# Actuator.net
KiCad netlist of a schematic drawn in EAGLE
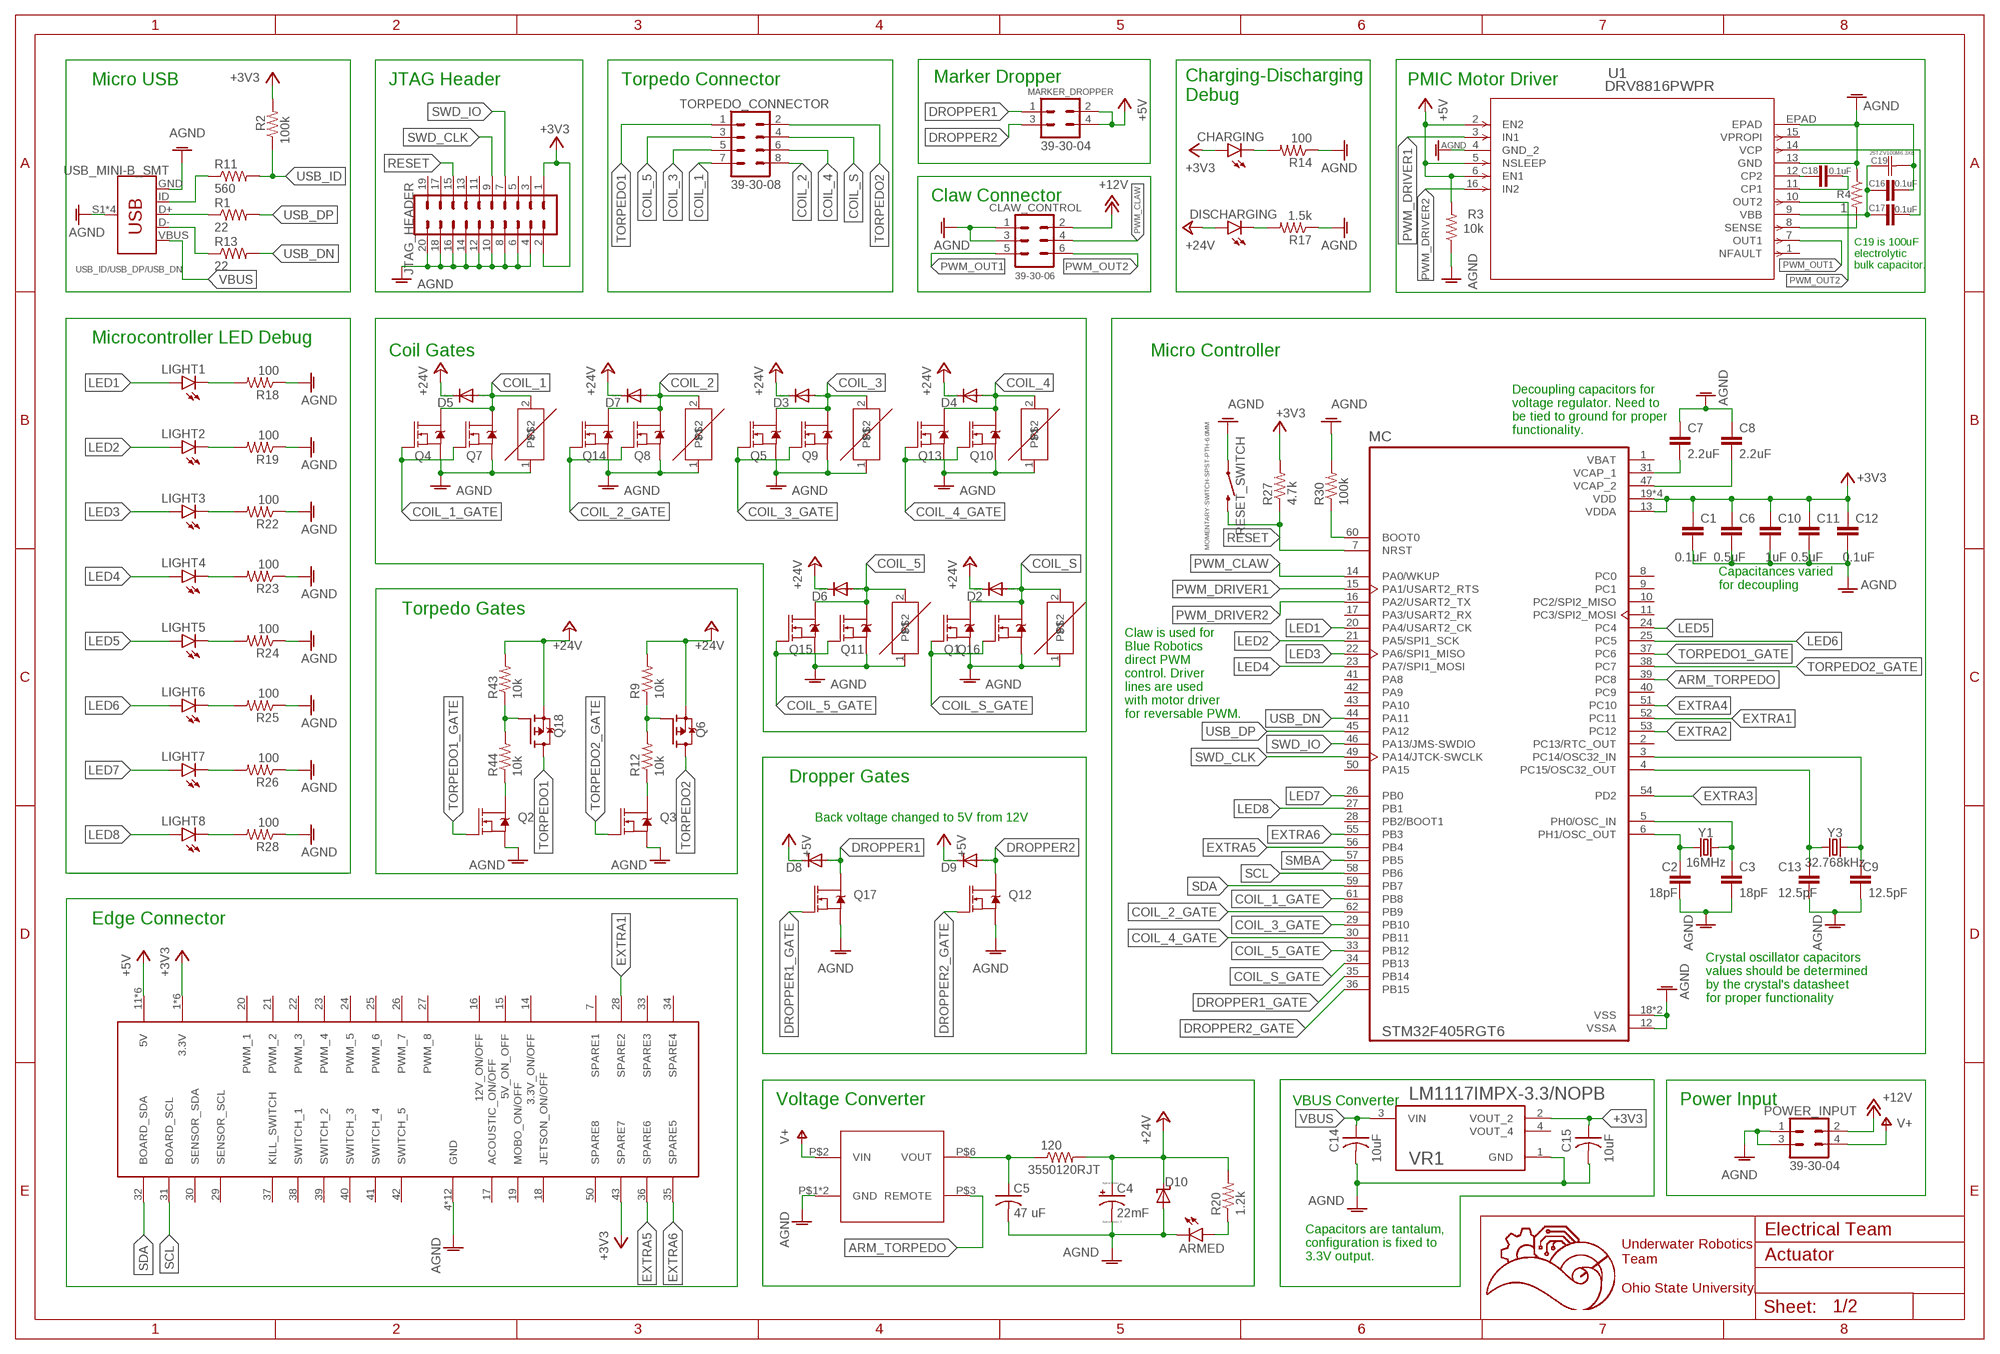
[diagram p0: schematic, sheet 1]
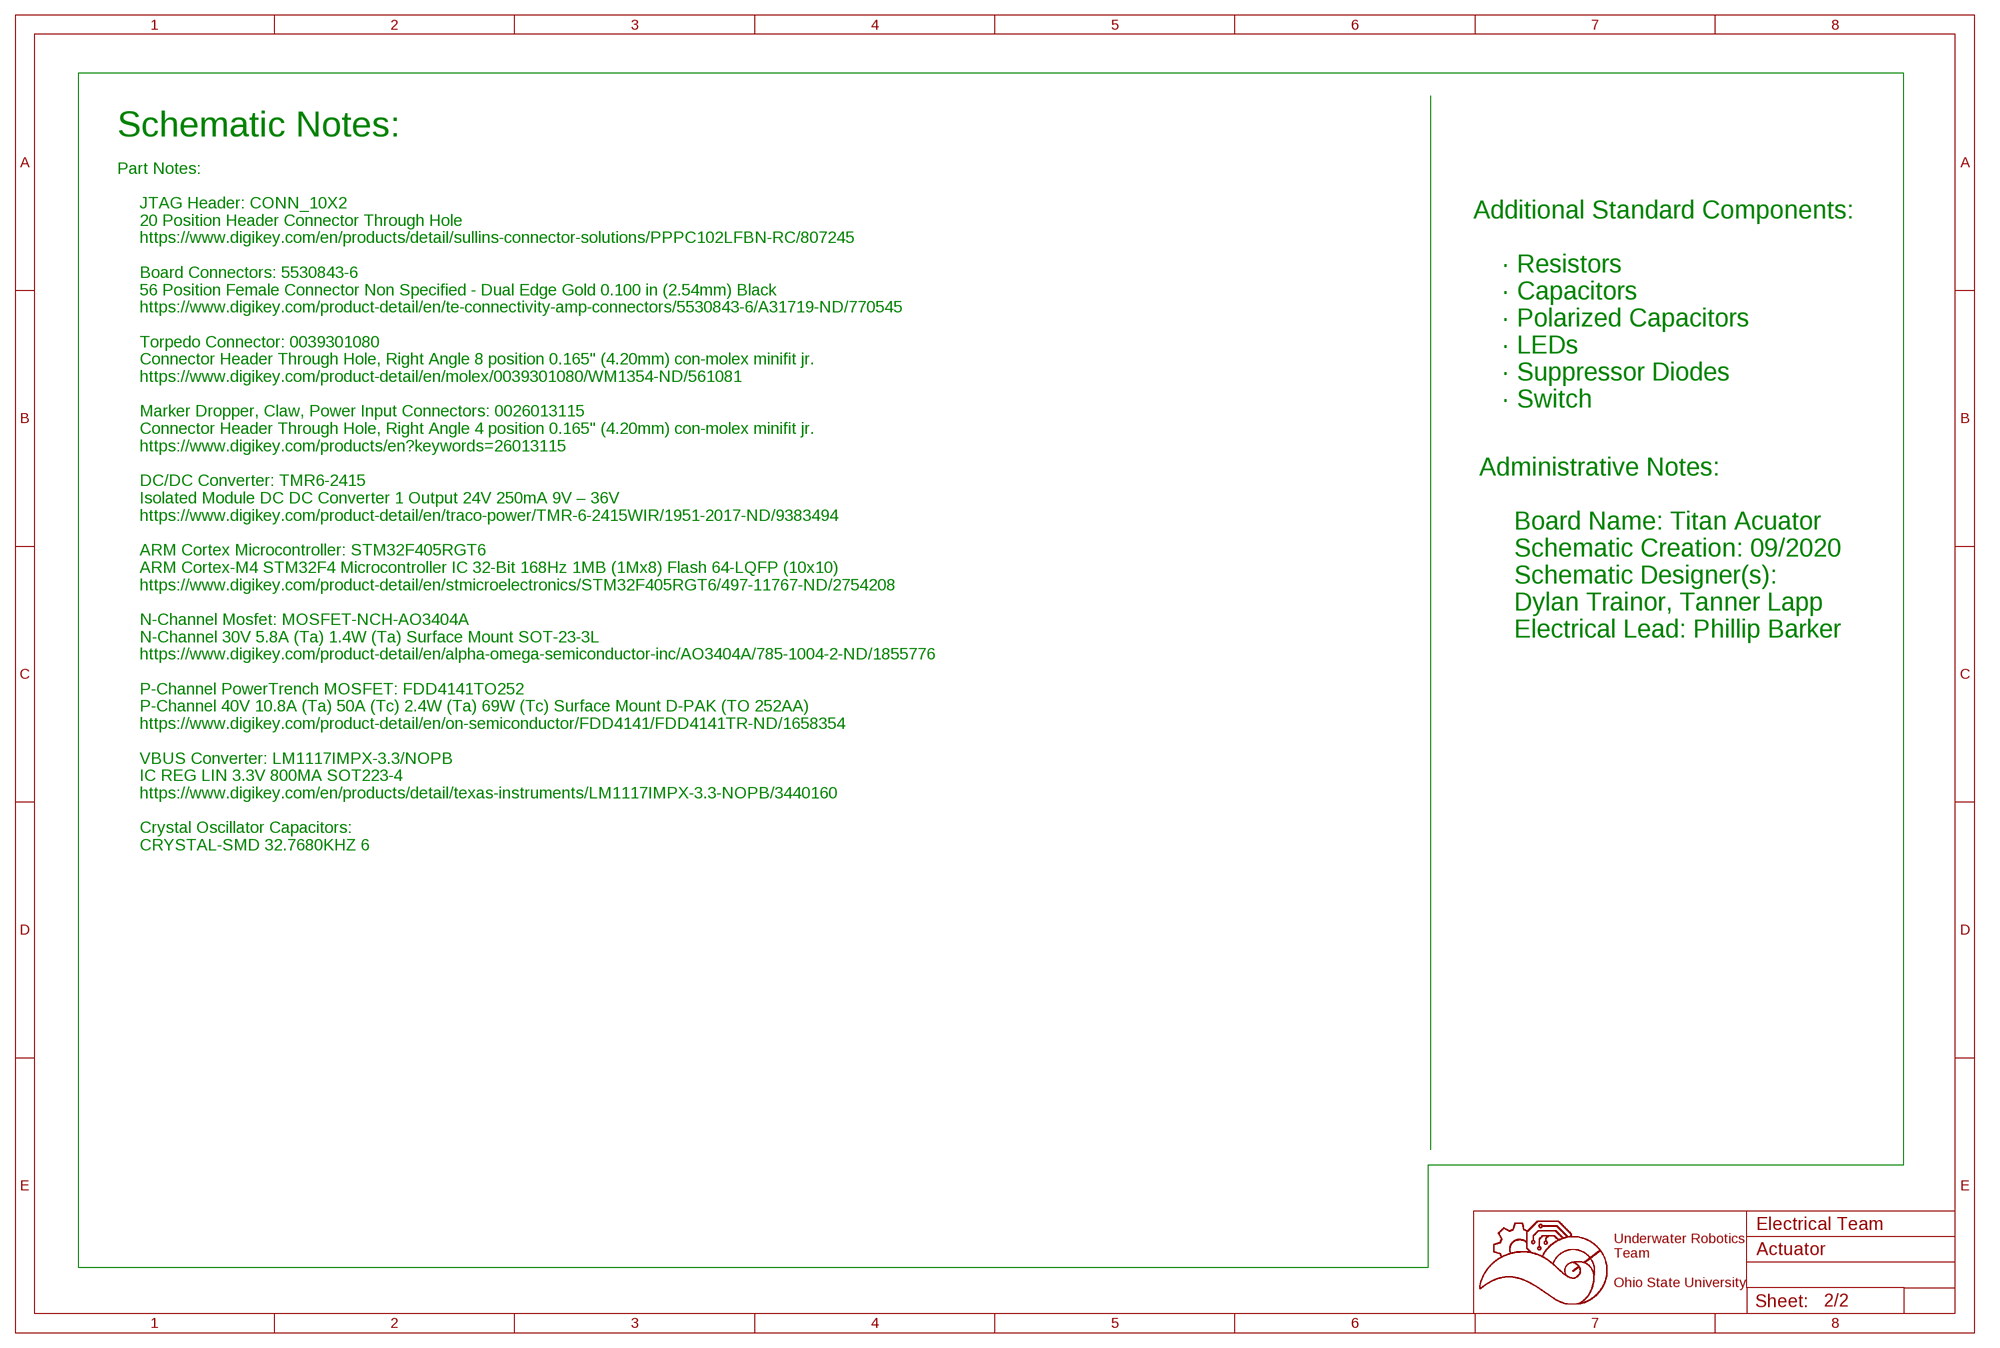
[diagram p1: schematic, sheet 2]

(export (version "E")
  (design (tool "Eeschema 10.0.6"))
  (components
    (comp (ref "120")
      (value "3550120RJT")
      (footprint "eagle-import:3550120RJT")
      (libsource (lib "eagle-import") (part "3550120RJT"))
    )
    (comp (ref "ARMED")
      (value "LEDCHIPLED_0603")
      (footprint "eagle-import:CHIPLED_0603")
      (libsource (lib "eagle-import") (part "LEDCHIPLED_0603"))
    )
    (comp (ref "C1")
      (value "0.1uF")
      (footprint "eagle-import:C0603")
      (libsource (lib "eagle-import") (part "C-EUC0603"))
    )
    (comp (ref "C2")
      (value "18pF")
      (footprint "eagle-import:C0603")
      (libsource (lib "eagle-import") (part "C-EUC0603"))
    )
    (comp (ref "C3")
      (value "18pF")
      (footprint "eagle-import:C0603")
      (libsource (lib "eagle-import") (part "C-EUC0603"))
    )
    (comp (ref "C4")
      (value "22mF")
      (footprint "eagle-import:EB30D")
      (libsource (lib "eagle-import") (part "CPOL-USE10-30"))
    )
    (comp (ref "C5")
      (value "47 uF")
      (footprint "eagle-import:C1206K")
      (libsource (lib "eagle-import") (part "resistor_348_C-USC1206K"))
    )
    (comp (ref "C6")
      (value "0.5uF")
      (footprint "eagle-import:C0603")
      (libsource (lib "eagle-import") (part "C-EUC0603"))
    )
    (comp (ref "C7")
      (value "2.2uF")
      (footprint "eagle-import:C0603")
      (libsource (lib "eagle-import") (part "C-EUC0603"))
    )
    (comp (ref "C8")
      (value "2.2uF")
      (footprint "eagle-import:C0603")
      (libsource (lib "eagle-import") (part "C-EUC0603"))
    )
    (comp (ref "C9")
      (value "12.5pF")
      (footprint "eagle-import:C0603")
      (libsource (lib "eagle-import") (part "C-EUC0603"))
    )
    (comp (ref "C10")
      (value "1uF")
      (footprint "eagle-import:C0603")
      (libsource (lib "eagle-import") (part "C-EUC0603"))
    )
    (comp (ref "C11")
      (value "0.5uF")
      (footprint "eagle-import:C0603")
      (libsource (lib "eagle-import") (part "C-EUC0603"))
    )
    (comp (ref "C12")
      (value "0.1uF")
      (footprint "eagle-import:C0603")
      (libsource (lib "eagle-import") (part "C-EUC0603"))
    )
    (comp (ref "C13")
      (value "12.5pF")
      (footprint "eagle-import:C0603")
      (libsource (lib "eagle-import") (part "C-EUC0603"))
    )
    (comp (ref "C14")
      (value "10uF")
      (footprint "eagle-import:C0603")
      (libsource (lib "eagle-import") (part "C-USC0603"))
    )
    (comp (ref "C15")
      (value "10uF")
      (footprint "eagle-import:C0603")
      (libsource (lib "eagle-import") (part "C-USC0603"))
    )
    (comp (ref "C16")
      (value "0.1uF")
      (footprint "eagle-import:C0603")
      (libsource (lib "eagle-import") (part "C-EUC0603"))
    )
    (comp (ref "C17")
      (value "0.1uF")
      (footprint "eagle-import:C0603")
      (libsource (lib "eagle-import") (part "C-EUC0603"))
    )
    (comp (ref "C18")
      (value "0.1uF")
      (footprint "eagle-import:C0603")
      (libsource (lib "eagle-import") (part "C-EUC0603"))
    )
    (comp (ref "C19")
      (value "25TZV100M6.3X8")
      (footprint "eagle-import:CAP_J-V_6P3X8_RUB")
      (fields (field (name "COPYRIGHT") "Copyright (C) 2018 Accelerated Designs. All rights reserved"))
      (libsource (lib "eagle-import") (part "25TZV100M6.3X8"))
    )
    (comp (ref "CHARGING")
      (value "LEDCHIPLED_0603")
      (footprint "eagle-import:CHIPLED_0603")
      (libsource (lib "eagle-import") (part "LEDCHIPLED_0603"))
    )
    (comp (ref "CLAW_CONTROL")
      (value "39-30-06")
      (footprint "eagle-import:39-30-_06_")
      (libsource (lib "eagle-import") (part "39-30-?06?"))
    )
    (comp (ref "D2")
      (value "DIODE-SMB")
      (footprint "eagle-import:SMB")
      (libsource (lib "eagle-import") (part "DIODE-SMB"))
    )
    (comp (ref "D3")
      (value "DIODE-SMB")
      (footprint "eagle-import:SMB")
      (libsource (lib "eagle-import") (part "DIODE-SMB"))
    )
    (comp (ref "D4")
      (value "DIODE-SMB")
      (footprint "eagle-import:SMB")
      (libsource (lib "eagle-import") (part "DIODE-SMB"))
    )
    (comp (ref "D5")
      (value "DIODE-SMB")
      (footprint "eagle-import:SMB")
      (libsource (lib "eagle-import") (part "DIODE-SMB"))
    )
    (comp (ref "D6")
      (value "DIODE-SMB")
      (footprint "eagle-import:SMB")
      (libsource (lib "eagle-import") (part "DIODE-SMB"))
    )
    (comp (ref "D7")
      (value "DIODE-SMB")
      (footprint "eagle-import:SMB")
      (libsource (lib "eagle-import") (part "DIODE-SMB"))
    )
    (comp (ref "D8")
      (value "DIODE-SMB")
      (footprint "eagle-import:SMB")
      (libsource (lib "eagle-import") (part "DIODE-SMB"))
    )
    (comp (ref "D9")
      (value "DIODE-SMB")
      (footprint "eagle-import:SMB")
      (libsource (lib "eagle-import") (part "DIODE-SMB"))
    )
    (comp (ref "D10")
      (value "SUPPRESSOR-SMBJ")
      (footprint "eagle-import:SMBJ")
      (libsource (lib "eagle-import") (part "SUPPRESSOR-SMBJ"))
    )
    (comp (ref "DISCHARGING")
      (value "LEDCHIPLED_0603")
      (footprint "eagle-import:CHIPLED_0603")
      (libsource (lib "eagle-import") (part "LEDCHIPLED_0603"))
    )
    (comp (ref "JTAG_HEADER")
      (value "CONN_10X2")
      (footprint "eagle-import:2X10")
      (libsource (lib "eagle-import") (part "CONN_10X2"))
    )
    (comp (ref "LIGHT1")
      (value "LEDCHIPLED_0603")
      (footprint "eagle-import:CHIPLED_0603")
      (libsource (lib "eagle-import") (part "LEDCHIPLED_0603"))
    )
    (comp (ref "LIGHT2")
      (value "LEDCHIPLED_0603")
      (footprint "eagle-import:CHIPLED_0603")
      (libsource (lib "eagle-import") (part "LEDCHIPLED_0603"))
    )
    (comp (ref "LIGHT3")
      (value "LEDCHIPLED_0603")
      (footprint "eagle-import:CHIPLED_0603")
      (libsource (lib "eagle-import") (part "LEDCHIPLED_0603"))
    )
    (comp (ref "LIGHT4")
      (value "LEDCHIPLED_0603")
      (footprint "eagle-import:CHIPLED_0603")
      (libsource (lib "eagle-import") (part "LEDCHIPLED_0603"))
    )
    (comp (ref "LIGHT5")
      (value "LEDCHIPLED_0603")
      (footprint "eagle-import:CHIPLED_0603")
      (libsource (lib "eagle-import") (part "LEDCHIPLED_0603"))
    )
    (comp (ref "LIGHT6")
      (value "LEDCHIPLED_0603")
      (footprint "eagle-import:CHIPLED_0603")
      (libsource (lib "eagle-import") (part "LEDCHIPLED_0603"))
    )
    (comp (ref "LIGHT7")
      (value "LEDCHIPLED_0603")
      (footprint "eagle-import:CHIPLED_0603")
      (libsource (lib "eagle-import") (part "LEDCHIPLED_0603"))
    )
    (comp (ref "LIGHT8")
      (value "LEDCHIPLED_0603")
      (footprint "eagle-import:CHIPLED_0603")
      (libsource (lib "eagle-import") (part "LEDCHIPLED_0603"))
    )
    (comp (ref "MARKER_DROPPER")
      (value "39-30-04")
      (footprint "eagle-import:39-30-_04_")
      (libsource (lib "eagle-import") (part "39-30-?04?"))
    )
    (comp (ref "MC")
      (value "STM32F405RGT6")
      (footprint "eagle-import:QFP50P1200X1200X160-64N")
      (fields (field (name "MF") "STMicroelectronics"))
      (libsource (lib "eagle-import") (part "STM32F405RGT6"))
    )
    (comp (ref "POWER_INPUT")
      (value "39-30-04")
      (footprint "eagle-import:39-30-_04_")
      (libsource (lib "eagle-import") (part "39-30-?04?"))
    )
    (comp (ref "Q1")
      (value "MOSFET-NCH-AO3404A")
      (footprint "eagle-import:SOT23-3")
      (libsource (lib "eagle-import") (part "MOSFET-NCH-AO3404A"))
    )
    (comp (ref "Q2")
      (value "MOSFET-NCH-AO3404A")
      (footprint "eagle-import:SOT23-3")
      (libsource (lib "eagle-import") (part "MOSFET-NCH-AO3404A"))
    )
    (comp (ref "Q3")
      (value "MOSFET-NCH-AO3404A")
      (footprint "eagle-import:SOT23-3")
      (libsource (lib "eagle-import") (part "MOSFET-NCH-AO3404A"))
    )
    (comp (ref "Q4")
      (value "MOSFET-NCH-AO3404A")
      (footprint "eagle-import:SOT23-3")
      (libsource (lib "eagle-import") (part "MOSFET-NCH-AO3404A"))
    )
    (comp (ref "Q5")
      (value "MOSFET-NCH-AO3404A")
      (footprint "eagle-import:SOT23-3")
      (libsource (lib "eagle-import") (part "MOSFET-NCH-AO3404A"))
    )
    (comp (ref "Q6")
      (value "FDD4141TO252")
      (footprint "eagle-import:TO252")
      (libsource (lib "eagle-import") (part "FDD4141TO252"))
    )
    (comp (ref "Q7")
      (value "MOSFET-NCH-AO3404A")
      (footprint "eagle-import:SOT23-3")
      (libsource (lib "eagle-import") (part "MOSFET-NCH-AO3404A"))
    )
    (comp (ref "Q8")
      (value "MOSFET-NCH-AO3404A")
      (footprint "eagle-import:SOT23-3")
      (libsource (lib "eagle-import") (part "MOSFET-NCH-AO3404A"))
    )
    (comp (ref "Q9")
      (value "MOSFET-NCH-AO3404A")
      (footprint "eagle-import:SOT23-3")
      (libsource (lib "eagle-import") (part "MOSFET-NCH-AO3404A"))
    )
    (comp (ref "Q10")
      (value "MOSFET-NCH-AO3404A")
      (footprint "eagle-import:SOT23-3")
      (libsource (lib "eagle-import") (part "MOSFET-NCH-AO3404A"))
    )
    (comp (ref "Q11")
      (value "MOSFET-NCH-AO3404A")
      (footprint "eagle-import:SOT23-3")
      (libsource (lib "eagle-import") (part "MOSFET-NCH-AO3404A"))
    )
    (comp (ref "Q12")
      (value "MOSFET-NCH-AO3404A")
      (footprint "eagle-import:SOT23-3")
      (libsource (lib "eagle-import") (part "MOSFET-NCH-AO3404A"))
    )
    (comp (ref "Q13")
      (value "MOSFET-NCH-AO3404A")
      (footprint "eagle-import:SOT23-3")
      (libsource (lib "eagle-import") (part "MOSFET-NCH-AO3404A"))
    )
    (comp (ref "Q14")
      (value "MOSFET-NCH-AO3404A")
      (footprint "eagle-import:SOT23-3")
      (libsource (lib "eagle-import") (part "MOSFET-NCH-AO3404A"))
    )
    (comp (ref "Q15")
      (value "MOSFET-NCH-AO3404A")
      (footprint "eagle-import:SOT23-3")
      (libsource (lib "eagle-import") (part "MOSFET-NCH-AO3404A"))
    )
    (comp (ref "Q16")
      (value "MOSFET-NCH-AO3404A")
      (footprint "eagle-import:SOT23-3")
      (libsource (lib "eagle-import") (part "MOSFET-NCH-AO3404A"))
    )
    (comp (ref "Q17")
      (value "MOSFET-NCH-AO3404A")
      (footprint "eagle-import:SOT23-3")
      (libsource (lib "eagle-import") (part "MOSFET-NCH-AO3404A"))
    )
    (comp (ref "Q18")
      (value "FDD4141TO252")
      (footprint "eagle-import:TO252")
      (libsource (lib "eagle-import") (part "FDD4141TO252"))
    )
    (comp (ref "R1")
      (value "22")
      (footprint "eagle-import:R0603")
      (libsource (lib "eagle-import") (part "R-US_R0603"))
    )
    (comp (ref "R2")
      (value "100k")
      (footprint "eagle-import:R0603")
      (libsource (lib "eagle-import") (part "R-US_R0603"))
    )
    (comp (ref "R3")
      (value "10k")
      (footprint "eagle-import:R0603")
      (libsource (lib "eagle-import") (part "resistor_348_R-US_R0603"))
    )
    (comp (ref "R4")
      (value "1")
      (footprint "eagle-import:R0805")
      (libsource (lib "eagle-import") (part "resistor_348_R-US_R0805"))
    )
    (comp (ref "R9")
      (value "10k")
      (footprint "eagle-import:R0603")
      (libsource (lib "eagle-import") (part "resistor_348_R-US_R0603"))
    )
    (comp (ref "R11")
      (value "560")
      (footprint "eagle-import:R0603")
      (libsource (lib "eagle-import") (part "R-US_R0603"))
    )
    (comp (ref "R12")
      (value "10k")
      (footprint "eagle-import:R0603")
      (libsource (lib "eagle-import") (part "resistor_348_R-US_R0603"))
    )
    (comp (ref "R13")
      (value "22")
      (footprint "eagle-import:R0603")
      (libsource (lib "eagle-import") (part "R-US_R0603"))
    )
    (comp (ref "R14")
      (value "100")
      (footprint "eagle-import:R0805")
      (libsource (lib "eagle-import") (part "resistor_348_R-US_R0805"))
    )
    (comp (ref "R17")
      (value "1.5k")
      (footprint "eagle-import:R0805")
      (libsource (lib "eagle-import") (part "resistor_348_R-US_R0805"))
    )
    (comp (ref "R18")
      (value "100")
      (footprint "eagle-import:R0805")
      (libsource (lib "eagle-import") (part "resistor_348_R-US_R0805"))
    )
    (comp (ref "R19")
      (value "100")
      (footprint "eagle-import:R0805")
      (libsource (lib "eagle-import") (part "resistor_348_R-US_R0805"))
    )
    (comp (ref "R20")
      (value "1.2k")
      (footprint "eagle-import:R0805")
      (libsource (lib "eagle-import") (part "resistor_348_R-US_R0805"))
    )
    (comp (ref "R22")
      (value "100")
      (footprint "eagle-import:R0805")
      (libsource (lib "eagle-import") (part "resistor_348_R-US_R0805"))
    )
    (comp (ref "R23")
      (value "100")
      (footprint "eagle-import:R0805")
      (libsource (lib "eagle-import") (part "resistor_348_R-US_R0805"))
    )
    (comp (ref "R24")
      (value "100")
      (footprint "eagle-import:R0805")
      (libsource (lib "eagle-import") (part "resistor_348_R-US_R0805"))
    )
    (comp (ref "R25")
      (value "100")
      (footprint "eagle-import:R0805")
      (libsource (lib "eagle-import") (part "resistor_348_R-US_R0805"))
    )
    (comp (ref "R26")
      (value "100")
      (footprint "eagle-import:R0805")
      (libsource (lib "eagle-import") (part "resistor_348_R-US_R0805"))
    )
    (comp (ref "R27")
      (value "4.7k")
      (footprint "eagle-import:R0603")
      (libsource (lib "eagle-import") (part "R-US_R0603"))
    )
    (comp (ref "R28")
      (value "100")
      (footprint "eagle-import:R0805")
      (libsource (lib "eagle-import") (part "resistor_348_R-US_R0805"))
    )
    (comp (ref "R30")
      (value "100k")
      (footprint "eagle-import:R0603")
      (libsource (lib "eagle-import") (part "R-US_R0603"))
    )
    (comp (ref "R43")
      (value "10k")
      (footprint "eagle-import:R0603")
      (libsource (lib "eagle-import") (part "resistor_348_R-US_R0603"))
    )
    (comp (ref "R44")
      (value "10k")
      (footprint "eagle-import:R0603")
      (libsource (lib "eagle-import") (part "resistor_348_R-US_R0603"))
    )
    (comp (ref "RESET_SWITCH")
      (value "MOMENTARY-SWITCH-SPST-PTH-6.0MM")
      (footprint "eagle-import:TACTILE_SWITCH_PTH_6.0MM")
      (libsource (lib "eagle-import") (part "MOMENTARY-SWITCH-SPST-PTH-6.0MM"))
    )
    (comp (ref "TORPEDO_CONNECTOR")
      (value "39-30-08")
      (footprint "eagle-import:39-30-_08_")
      (libsource (lib "eagle-import") (part "39-30-?08?"))
    )
    (comp (ref "U$1")
      (value "5530843-EDGE")
      (footprint "eagle-import:5530843-6-BOARDFINGERS")
      (libsource (lib "eagle-import") (part "5530843-EDGE"))
    )
    (comp (ref "U$2")
      (value "ERZ-VF2M270ERZ-VF2M270")
      (footprint "eagle-import:RESM8060X320N")
      (libsource (lib "eagle-import") (part "ERZ-VF2M270ERZ-VF2M270"))
    )
    (comp (ref "U$3")
      (value "ERZ-VF2M270ERZ-VF2M270")
      (footprint "eagle-import:RESM8060X320N")
      (libsource (lib "eagle-import") (part "ERZ-VF2M270ERZ-VF2M270"))
    )
    (comp (ref "U$4")
      (value "ERZ-VF2M270ERZ-VF2M270")
      (footprint "eagle-import:RESM8060X320N")
      (libsource (lib "eagle-import") (part "ERZ-VF2M270ERZ-VF2M270"))
    )
    (comp (ref "U$5")
      (value "ERZ-VF2M270ERZ-VF2M270")
      (footprint "eagle-import:RESM8060X320N")
      (libsource (lib "eagle-import") (part "ERZ-VF2M270ERZ-VF2M270"))
    )
    (comp (ref "U$6")
      (value "TMR6-2415")
      (footprint "eagle-import:TMR6-2415")
      (libsource (lib "eagle-import") (part "TMR6-2415"))
    )
    (comp (ref "U$7")
      (value "ERZ-VF2M270ERZ-VF2M270")
      (footprint "eagle-import:RESM8060X320N")
      (libsource (lib "eagle-import") (part "ERZ-VF2M270ERZ-VF2M270"))
    )
    (comp (ref "U$8")
      (value "ERZ-VF2M270ERZ-VF2M270")
      (footprint "eagle-import:RESM8060X320N")
      (libsource (lib "eagle-import") (part "ERZ-VF2M270ERZ-VF2M270"))
    )
    (comp (ref "U1")
      (value "DRV8816PWPR")
      (footprint "eagle-import:PWP_16")
      (libsource (lib "eagle-import") (part "DRV8816PWPR"))
    )
    (comp (ref "USB_ID/USB_DP/USB_DN")
      (value "USB_MINI-B_SMT")
      (footprint "eagle-import:USB-MINIB")
      (libsource (lib "eagle-import") (part "USB_MINI-B_SMT"))
    )
    (comp (ref "VR1")
      (value "LM1117IMPX-3.3/NOPB")
      (footprint "eagle-import:VREG_LM1117IMPX-3.3_NOPB")
      (fields (field (name "MF") "Texas Instruments"))
      (libsource (lib "eagle-import") (part "LM1117IMPX-3.3/NOPB"))
    )
    (comp (ref "Y1")
      (value "16MHz")
      (footprint "eagle-import:HC49US")
      (libsource (lib "eagle-import") (part "CRYSTAL-16MHZPTH-HC49US"))
    )
    (comp (ref "Y3")
      (value "32.768kHz")
      (footprint "eagle-import:CRYSTAL-SMD-3.2X1.5MM")
      (libsource (lib "eagle-import") (part "CRYSTAL-32.768KHZSMD-3.2X1.5"))
    )
  )
  (nets
    (net (code "1") (name "+3V3") (class "Default")
      (node (ref "C1") (pin "1") (pinfunction "1_1") (pintype "passive"))
      (node (ref "C10") (pin "1") (pinfunction "1_1") (pintype "passive"))
      (node (ref "C11") (pin "1") (pinfunction "1_1") (pintype "passive"))
      (node (ref "C12") (pin "1") (pinfunction "1_1") (pintype "passive"))
      (node (ref "C15") (pin "1") (pinfunction "1_1") (pintype "passive"))
      (node (ref "C6") (pin "1") (pinfunction "1_1") (pintype "passive"))
      (node (ref "CHARGING") (pin "A") (pinfunction "A_A") (pintype "passive"))
      (node (ref "JTAG_HEADER") (pin "1") (pinfunction "1_1") (pintype "passive"))
      (node (ref "JTAG_HEADER") (pin "2") (pinfunction "2_2") (pintype "passive"))
      (node (ref "MC") (pin "13") (pinfunction "VDDA_13") (pintype "power_in"))
      (node (ref "MC") (pin "19") (pinfunction "VDD_19") (pintype "power_in"))
      (node (ref "MC") (pin "32") (pinfunction "VDD_32") (pintype "power_in"))
      (node (ref "MC") (pin "48") (pinfunction "VDD_48") (pintype "power_in"))
      (node (ref "MC") (pin "64") (pinfunction "VDD_64") (pintype "power_in"))
      (node (ref "R2") (pin "2") (pinfunction "2_2") (pintype "passive"))
      (node (ref "R27") (pin "2") (pinfunction "2_2") (pintype "passive"))
      (node (ref "U$1") (pin "1") (pinfunction "3.3V_1") (pintype "bidirectional"))
      (node (ref "U$1") (pin "2") (pinfunction "3.3V_2") (pintype "bidirectional"))
      (node (ref "U$1") (pin "3") (pinfunction "3.3V_3") (pintype "bidirectional"))
      (node (ref "U$1") (pin "43") (pinfunction "SPARE7_43") (pintype "bidirectional"))
      (node (ref "U$1") (pin "54") (pinfunction "3.3V_54") (pintype "bidirectional"))
      (node (ref "U$1") (pin "55") (pinfunction "3.3V_55") (pintype "bidirectional"))
      (node (ref "U$1") (pin "56") (pinfunction "3.3V_56") (pintype "bidirectional"))
      (node (ref "VR1") (pin "2") (pinfunction "VOUT_2_2") (pintype "output"))
    )
    (net (code "2") (name "+5V") (class "Default")
      (node (ref "D8") (pin "C") (pinfunction "C_C") (pintype "passive"))
      (node (ref "D9") (pin "C") (pinfunction "C_C") (pintype "passive"))
      (node (ref "MARKER_DROPPER") (pin "2") (pinfunction "2_2") (pintype "passive"))
      (node (ref "MARKER_DROPPER") (pin "4") (pinfunction "4_4") (pintype "passive"))
      (node (ref "R3") (pin "2") (pinfunction "2_2") (pintype "passive"))
      (node (ref "U$1") (pin "11") (pinfunction "5V_11") (pintype "bidirectional"))
      (node (ref "U$1") (pin "12") (pinfunction "5V_12") (pintype "bidirectional"))
      (node (ref "U$1") (pin "13") (pinfunction "5V_13") (pintype "bidirectional"))
      (node (ref "U$1") (pin "44") (pinfunction "5V_44") (pintype "bidirectional"))
      (node (ref "U$1") (pin "45") (pinfunction "5V_45") (pintype "bidirectional"))
      (node (ref "U$1") (pin "46") (pinfunction "5V_46") (pintype "bidirectional"))
      (node (ref "U1") (pin "2") (pinfunction "EN2_2") (pintype "input"))
      (node (ref "U1") (pin "5") (pinfunction "NSLEEP_5") (pintype "input"))
      (node (ref "U1") (pin "6") (pinfunction "EN1_6") (pintype "input"))
    )
    (net (code "3") (name "+12V") (class "Default")
      (node (ref "CLAW_CONTROL") (pin "2") (pinfunction "2_2") (pintype "passive"))
      (node (ref "POWER_INPUT") (pin "2") (pinfunction "2_2") (pintype "passive"))
    )
    (net (code "4") (name "+24V") (class "Default")
      (node (ref "120") (pin "P$2") (pinfunction "2_P$2") (pintype "passive"))
      (node (ref "C4") (pin "+") (pinfunction "+_+") (pintype "passive"))
      (node (ref "D10") (pin "C") (pinfunction "C_C") (pintype "passive"))
      (node (ref "D2") (pin "C") (pinfunction "C_C") (pintype "passive"))
      (node (ref "D3") (pin "C") (pinfunction "C_C") (pintype "passive"))
      (node (ref "D4") (pin "C") (pinfunction "C_C") (pintype "passive"))
      (node (ref "D5") (pin "C") (pinfunction "C_C") (pintype "passive"))
      (node (ref "D6") (pin "C") (pinfunction "C_C") (pintype "passive"))
      (node (ref "D7") (pin "C") (pinfunction "C_C") (pintype "passive"))
      (node (ref "DISCHARGING") (pin "A") (pinfunction "A_A") (pintype "passive"))
      (node (ref "Q18") (pin "2") (pinfunction "S_2") (pintype "passive"))
      (node (ref "Q6") (pin "2") (pinfunction "S_2") (pintype "passive"))
      (node (ref "R20") (pin "2") (pinfunction "2_2") (pintype "passive"))
      (node (ref "R43") (pin "2") (pinfunction "2_2") (pintype "passive"))
      (node (ref "R9") (pin "2") (pinfunction "2_2") (pintype "passive"))
    )
    (net (code "5") (name "AGND") (class "Default")
      (node (ref "ARMED") (pin "C") (pinfunction "C_C") (pintype "passive"))
      (node (ref "C1") (pin "2") (pinfunction "2_2") (pintype "passive"))
      (node (ref "C10") (pin "2") (pinfunction "2_2") (pintype "passive"))
      (node (ref "C11") (pin "2") (pinfunction "2_2") (pintype "passive"))
      (node (ref "C12") (pin "2") (pinfunction "2_2") (pintype "passive"))
      (node (ref "C13") (pin "2") (pinfunction "2_2") (pintype "passive"))
      (node (ref "C14") (pin "2") (pinfunction "2_2") (pintype "passive"))
      (node (ref "C15") (pin "2") (pinfunction "2_2") (pintype "passive"))
      (node (ref "C16") (pin "2") (pinfunction "2_2") (pintype "passive"))
      (node (ref "C19") (pin "2") (pinfunction "2_2") (pintype "passive"))
      (node (ref "C2") (pin "2") (pinfunction "2_2") (pintype "passive"))
      (node (ref "C3") (pin "2") (pinfunction "2_2") (pintype "passive"))
      (node (ref "C4") (pin "-") (pinfunction "-_-") (pintype "passive"))
      (node (ref "C5") (pin "2") (pinfunction "2_2") (pintype "passive"))
      (node (ref "C6") (pin "2") (pinfunction "2_2") (pintype "passive"))
      (node (ref "C7") (pin "1") (pinfunction "1_1") (pintype "passive"))
      (node (ref "C8") (pin "1") (pinfunction "1_1") (pintype "passive"))
      (node (ref "C9") (pin "2") (pinfunction "2_2") (pintype "passive"))
      (node (ref "CLAW_CONTROL") (pin "1") (pinfunction "1_1") (pintype "passive"))
      (node (ref "CLAW_CONTROL") (pin "3") (pinfunction "3_3") (pintype "passive"))
      (node (ref "D10") (pin "A") (pinfunction "A_A") (pintype "passive"))
      (node (ref "JTAG_HEADER") (pin "10") (pinfunction "10_10") (pintype "passive"))
      (node (ref "JTAG_HEADER") (pin "12") (pinfunction "12_12") (pintype "passive"))
      (node (ref "JTAG_HEADER") (pin "14") (pinfunction "14_14") (pintype "passive"))
      (node (ref "JTAG_HEADER") (pin "16") (pinfunction "16_16") (pintype "passive"))
      (node (ref "JTAG_HEADER") (pin "18") (pinfunction "18_18") (pintype "passive"))
      (node (ref "JTAG_HEADER") (pin "20") (pinfunction "20_20") (pintype "passive"))
      (node (ref "JTAG_HEADER") (pin "4") (pinfunction "4_4") (pintype "passive"))
      (node (ref "JTAG_HEADER") (pin "6") (pinfunction "6_6") (pintype "passive"))
      (node (ref "JTAG_HEADER") (pin "8") (pinfunction "8_8") (pintype "passive"))
      (node (ref "MC") (pin "12") (pinfunction "VSSA_12") (pintype "power_in"))
      (node (ref "MC") (pin "18") (pinfunction "VSS_18") (pintype "power_in"))
      (node (ref "MC") (pin "63") (pinfunction "VSS_63") (pintype "power_in"))
      (node (ref "POWER_INPUT") (pin "1") (pinfunction "1_1") (pintype "passive"))
      (node (ref "POWER_INPUT") (pin "3") (pinfunction "3_3") (pintype "passive"))
      (node (ref "Q1") (pin "2") (pinfunction "S_2") (pintype "bidirectional"))
      (node (ref "Q10") (pin "2") (pinfunction "S_2") (pintype "bidirectional"))
      (node (ref "Q11") (pin "2") (pinfunction "S_2") (pintype "bidirectional"))
      (node (ref "Q12") (pin "2") (pinfunction "S_2") (pintype "bidirectional"))
      (node (ref "Q13") (pin "2") (pinfunction "S_2") (pintype "bidirectional"))
      (node (ref "Q14") (pin "2") (pinfunction "S_2") (pintype "bidirectional"))
      (node (ref "Q15") (pin "2") (pinfunction "S_2") (pintype "bidirectional"))
      (node (ref "Q16") (pin "2") (pinfunction "S_2") (pintype "bidirectional"))
      (node (ref "Q17") (pin "2") (pinfunction "S_2") (pintype "bidirectional"))
      (node (ref "Q2") (pin "2") (pinfunction "S_2") (pintype "bidirectional"))
      (node (ref "Q3") (pin "2") (pinfunction "S_2") (pintype "bidirectional"))
      (node (ref "Q4") (pin "2") (pinfunction "S_2") (pintype "bidirectional"))
      (node (ref "Q5") (pin "2") (pinfunction "S_2") (pintype "bidirectional"))
      (node (ref "Q7") (pin "2") (pinfunction "S_2") (pintype "bidirectional"))
      (node (ref "Q8") (pin "2") (pinfunction "S_2") (pintype "bidirectional"))
      (node (ref "Q9") (pin "2") (pinfunction "S_2") (pintype "bidirectional"))
      (node (ref "R14") (pin "1") (pinfunction "1_1") (pintype "passive"))
      (node (ref "R17") (pin "1") (pinfunction "1_1") (pintype "passive"))
      (node (ref "R18") (pin "1") (pinfunction "1_1") (pintype "passive"))
      (node (ref "R19") (pin "1") (pinfunction "1_1") (pintype "passive"))
      (node (ref "R22") (pin "1") (pinfunction "1_1") (pintype "passive"))
      (node (ref "R23") (pin "1") (pinfunction "1_1") (pintype "passive"))
      (node (ref "R24") (pin "1") (pinfunction "1_1") (pintype "passive"))
      (node (ref "R25") (pin "1") (pinfunction "1_1") (pintype "passive"))
      (node (ref "R26") (pin "1") (pinfunction "1_1") (pintype "passive"))
      (node (ref "R28") (pin "1") (pinfunction "1_1") (pintype "passive"))
      (node (ref "R3") (pin "1") (pinfunction "1_1") (pintype "passive"))
      (node (ref "R30") (pin "2") (pinfunction "2_2") (pintype "passive"))
      (node (ref "R4") (pin "1") (pinfunction "1_1") (pintype "passive"))
      (node (ref "RESET_SWITCH") (pin "1") (pinfunction "1_1") (pintype "passive"))
      (node (ref "U$1") (pin "10") (pinfunction "GND_10") (pintype "bidirectional"))
      (node (ref "U$1") (pin "4") (pinfunction "GND_4") (pintype "bidirectional"))
      (node (ref "U$1") (pin "47") (pinfunction "GND_47") (pintype "bidirectional"))
      (node (ref "U$1") (pin "48") (pinfunction "GND_48") (pintype "bidirectional"))
      (node (ref "U$1") (pin "49") (pinfunction "GND_49") (pintype "bidirectional"))
      (node (ref "U$1") (pin "5") (pinfunction "GND_5") (pintype "bidirectional"))
      (node (ref "U$1") (pin "51") (pinfunction "GND_51") (pintype "bidirectional"))
      (node (ref "U$1") (pin "52") (pinfunction "GND_52") (pintype "bidirectional"))
      (node (ref "U$1") (pin "53") (pinfunction "GND_53") (pintype "bidirectional"))
      (node (ref "U$1") (pin "6") (pinfunction "GND_6") (pintype "bidirectional"))
      (node (ref "U$1") (pin "8") (pinfunction "GND_8") (pintype "bidirectional"))
      (node (ref "U$1") (pin "9") (pinfunction "GND_9") (pintype "bidirectional"))
      (node (ref "U$2") (pin "1") (pinfunction "P$1_1") (pintype "bidirectional"))
      (node (ref "U$3") (pin "1") (pinfunction "P$1_1") (pintype "bidirectional"))
      (node (ref "U$4") (pin "1") (pinfunction "P$1_1") (pintype "bidirectional"))
      (node (ref "U$5") (pin "1") (pinfunction "P$1_1") (pintype "bidirectional"))
      (node (ref "U$6") (pin "P$1") (pinfunction "GND_P$1") (pintype "bidirectional"))
      (node (ref "U$6") (pin "P$7") (pinfunction "GND_P$7") (pintype "bidirectional"))
      (node (ref "U$7") (pin "1") (pinfunction "P$1_1") (pintype "bidirectional"))
      (node (ref "U$8") (pin "1") (pinfunction "P$1_1") (pintype "bidirectional"))
      (node (ref "U1") (pin "13") (pinfunction "GND_13") (pintype "power_in"))
      (node (ref "U1") (pin "4") (pinfunction "GND_2_4") (pintype "power_in"))
      (node (ref "U1") (pin "EPAD") (pinfunction "EPAD_EPAD") (pintype "passive"))
      (node (ref "USB_ID/USB_DP/USB_DN") (pin "GND") (pinfunction "GND_GND") (pintype "power_in"))
      (node (ref "USB_ID/USB_DP/USB_DN") (pin "S1") (pinfunction "SHIELD_S1") (pintype "bidirectional"))
      (node (ref "USB_ID/USB_DP/USB_DN") (pin "S2") (pinfunction "SHIELD_S2") (pintype "bidirectional"))
      (node (ref "USB_ID/USB_DP/USB_DN") (pin "S3") (pinfunction "SHIELD_S3") (pintype "bidirectional"))
      (node (ref "USB_ID/USB_DP/USB_DN") (pin "S4") (pinfunction "SHIELD_S4") (pintype "bidirectional"))
      (node (ref "VR1") (pin "1") (pinfunction "GND_1") (pintype "power_in"))
    )
    (net (code "6") (name "ARM_TORPEDO") (class "Default")
      (node (ref "MC") (pin "39") (pinfunction "PC8_39") (pintype "bidirectional"))
      (node (ref "U$6") (pin "P$3") (pinfunction "REMOTE_P$3") (pintype "bidirectional"))
    )
    (net (code "7") (name "COIL_1") (class "Default")
      (node (ref "D5") (pin "A") (pinfunction "A_A") (pintype "passive"))
      (node (ref "Q4") (pin "3") (pinfunction "D_3") (pintype "bidirectional"))
      (node (ref "Q7") (pin "3") (pinfunction "D_3") (pintype "bidirectional"))
      (node (ref "TORPEDO_CONNECTOR") (pin "7") (pinfunction "7_7") (pintype "passive"))
      (node (ref "U$8") (pin "2") (pinfunction "P$2_2") (pintype "bidirectional"))
    )
    (net (code "8") (name "COIL_1_GATE") (class "Default")
      (node (ref "MC") (pin "61") (pinfunction "PB8_61") (pintype "bidirectional"))
      (node (ref "Q4") (pin "1") (pinfunction "G_1") (pintype "bidirectional"))
      (node (ref "Q7") (pin "1") (pinfunction "G_1") (pintype "bidirectional"))
    )
    (net (code "9") (name "COIL_2") (class "Default")
      (node (ref "D7") (pin "A") (pinfunction "A_A") (pintype "passive"))
      (node (ref "Q14") (pin "3") (pinfunction "D_3") (pintype "bidirectional"))
      (node (ref "Q8") (pin "3") (pinfunction "D_3") (pintype "bidirectional"))
      (node (ref "TORPEDO_CONNECTOR") (pin "8") (pinfunction "8_8") (pintype "passive"))
      (node (ref "U$7") (pin "2") (pinfunction "P$2_2") (pintype "bidirectional"))
    )
    (net (code "10") (name "COIL_2_GATE") (class "Default")
      (node (ref "MC") (pin "62") (pinfunction "PB9_62") (pintype "bidirectional"))
      (node (ref "Q14") (pin "1") (pinfunction "G_1") (pintype "bidirectional"))
      (node (ref "Q8") (pin "1") (pinfunction "G_1") (pintype "bidirectional"))
    )
    (net (code "11") (name "COIL_3") (class "Default")
      (node (ref "D3") (pin "A") (pinfunction "A_A") (pintype "passive"))
      (node (ref "Q5") (pin "3") (pinfunction "D_3") (pintype "bidirectional"))
      (node (ref "Q9") (pin "3") (pinfunction "D_3") (pintype "bidirectional"))
      (node (ref "TORPEDO_CONNECTOR") (pin "5") (pinfunction "5_5") (pintype "passive"))
      (node (ref "U$5") (pin "2") (pinfunction "P$2_2") (pintype "bidirectional"))
    )
    (net (code "12") (name "COIL_3_GATE") (class "Default")
      (node (ref "MC") (pin "29") (pinfunction "PB10_29") (pintype "bidirectional"))
      (node (ref "Q5") (pin "1") (pinfunction "G_1") (pintype "bidirectional"))
      (node (ref "Q9") (pin "1") (pinfunction "G_1") (pintype "bidirectional"))
    )
    (net (code "13") (name "COIL_4") (class "Default")
      (node (ref "D4") (pin "A") (pinfunction "A_A") (pintype "passive"))
      (node (ref "Q10") (pin "3") (pinfunction "D_3") (pintype "bidirectional"))
      (node (ref "Q13") (pin "3") (pinfunction "D_3") (pintype "bidirectional"))
      (node (ref "TORPEDO_CONNECTOR") (pin "6") (pinfunction "6_6") (pintype "passive"))
      (node (ref "U$4") (pin "2") (pinfunction "P$2_2") (pintype "bidirectional"))
    )
    (net (code "14") (name "COIL_4_GATE") (class "Default")
      (node (ref "MC") (pin "30") (pinfunction "PB11_30") (pintype "bidirectional"))
      (node (ref "Q10") (pin "1") (pinfunction "G_1") (pintype "bidirectional"))
      (node (ref "Q13") (pin "1") (pinfunction "G_1") (pintype "bidirectional"))
    )
    (net (code "15") (name "COIL_5") (class "Default")
      (node (ref "D6") (pin "A") (pinfunction "A_A") (pintype "passive"))
      (node (ref "Q11") (pin "3") (pinfunction "D_3") (pintype "bidirectional"))
      (node (ref "Q15") (pin "3") (pinfunction "D_3") (pintype "bidirectional"))
      (node (ref "TORPEDO_CONNECTOR") (pin "3") (pinfunction "3_3") (pintype "passive"))
      (node (ref "U$3") (pin "2") (pinfunction "P$2_2") (pintype "bidirectional"))
    )
    (net (code "16") (name "COIL_5_GATE") (class "Default")
      (node (ref "MC") (pin "33") (pinfunction "PB12_33") (pintype "bidirectional"))
      (node (ref "Q11") (pin "1") (pinfunction "G_1") (pintype "bidirectional"))
      (node (ref "Q15") (pin "1") (pinfunction "G_1") (pintype "bidirectional"))
    )
    (net (code "17") (name "COIL_S") (class "Default")
      (node (ref "D2") (pin "A") (pinfunction "A_A") (pintype "passive"))
      (node (ref "Q1") (pin "3") (pinfunction "D_3") (pintype "bidirectional"))
      (node (ref "Q16") (pin "3") (pinfunction "D_3") (pintype "bidirectional"))
      (node (ref "TORPEDO_CONNECTOR") (pin "4") (pinfunction "4_4") (pintype "passive"))
      (node (ref "U$2") (pin "2") (pinfunction "P$2_2") (pintype "bidirectional"))
    )
    (net (code "18") (name "COIL_S_GATE") (class "Default")
      (node (ref "MC") (pin "34") (pinfunction "PB13_34") (pintype "bidirectional"))
      (node (ref "Q1") (pin "1") (pinfunction "G_1") (pintype "bidirectional"))
      (node (ref "Q16") (pin "1") (pinfunction "G_1") (pintype "bidirectional"))
    )
    (net (code "19") (name "DROPPER1") (class "Default")
      (node (ref "D8") (pin "A") (pinfunction "A_A") (pintype "passive"))
      (node (ref "MARKER_DROPPER") (pin "1") (pinfunction "1_1") (pintype "passive"))
      (node (ref "Q17") (pin "3") (pinfunction "D_3") (pintype "bidirectional"))
    )
    (net (code "20") (name "DROPPER1_GATE") (class "Default")
      (node (ref "MC") (pin "35") (pinfunction "PB14_35") (pintype "bidirectional"))
      (node (ref "Q17") (pin "1") (pinfunction "G_1") (pintype "bidirectional"))
    )
    (net (code "21") (name "DROPPER2") (class "Default")
      (node (ref "D9") (pin "A") (pinfunction "A_A") (pintype "passive"))
      (node (ref "MARKER_DROPPER") (pin "3") (pinfunction "3_3") (pintype "passive"))
      (node (ref "Q12") (pin "3") (pinfunction "D_3") (pintype "bidirectional"))
    )
    (net (code "22") (name "DROPPER2_GATE") (class "Default")
      (node (ref "MC") (pin "36") (pinfunction "PB15_36") (pintype "bidirectional"))
      (node (ref "Q12") (pin "1") (pinfunction "G_1") (pintype "bidirectional"))
    )
    (net (code "23") (name "EXTRA1") (class "Default")
      (node (ref "MC") (pin "52") (pinfunction "PC11_52") (pintype "bidirectional"))
      (node (ref "U$1") (pin "28") (pinfunction "SPARE2_28") (pintype "bidirectional"))
    )
    (net (code "24") (name "EXTRA2") (class "Default")
      (node (ref "MC") (pin "53") (pinfunction "PC12_53") (pintype "bidirectional"))
    )
    (net (code "25") (name "EXTRA3") (class "Default")
      (node (ref "MC") (pin "54") (pinfunction "PD2_54") (pintype "bidirectional"))
    )
    (net (code "26") (name "EXTRA4") (class "Default")
      (node (ref "MC") (pin "51") (pinfunction "PC10_51") (pintype "bidirectional"))
    )
    (net (code "27") (name "EXTRA5") (class "Default")
      (node (ref "MC") (pin "56") (pinfunction "PB4_56") (pintype "bidirectional"))
      (node (ref "U$1") (pin "36") (pinfunction "SPARE6_36") (pintype "bidirectional"))
    )
    (net (code "28") (name "EXTRA6") (class "Default")
      (node (ref "MC") (pin "55") (pinfunction "PB3_55") (pintype "bidirectional"))
      (node (ref "U$1") (pin "35") (pinfunction "SPARE5_35") (pintype "bidirectional"))
    )
    (net (code "29") (name "LED1") (class "Default")
      (node (ref "LIGHT1") (pin "A") (pinfunction "A_A") (pintype "passive"))
      (node (ref "MC") (pin "20") (pinfunction "PA4/USART2_CK_20") (pintype "bidirectional"))
    )
    (net (code "30") (name "LED2") (class "Default")
      (node (ref "LIGHT2") (pin "A") (pinfunction "A_A") (pintype "passive"))
      (node (ref "MC") (pin "21") (pinfunction "PA5/SPI1_SCK_21") (pintype "bidirectional"))
    )
    (net (code "31") (name "LED3") (class "Default")
      (node (ref "LIGHT3") (pin "A") (pinfunction "A_A") (pintype "passive"))
      (node (ref "MC") (pin "22") (pinfunction "PA6/SPI1_MISO_22") (pintype "bidirectional"))
    )
    (net (code "32") (name "LED4") (class "Default")
      (node (ref "LIGHT4") (pin "A") (pinfunction "A_A") (pintype "passive"))
      (node (ref "MC") (pin "23") (pinfunction "PA7/SPI1_MOSI_23") (pintype "bidirectional"))
    )
    (net (code "33") (name "LED5") (class "Default")
      (node (ref "LIGHT5") (pin "A") (pinfunction "A_A") (pintype "passive"))
      (node (ref "MC") (pin "24") (pinfunction "PC4_24") (pintype "bidirectional"))
    )
    (net (code "34") (name "LED6") (class "Default")
      (node (ref "LIGHT6") (pin "A") (pinfunction "A_A") (pintype "passive"))
      (node (ref "MC") (pin "25") (pinfunction "PC5_25") (pintype "bidirectional"))
    )
    (net (code "35") (name "LED7") (class "Default")
      (node (ref "LIGHT7") (pin "A") (pinfunction "A_A") (pintype "passive"))
      (node (ref "MC") (pin "26") (pinfunction "PB0_26") (pintype "bidirectional"))
    )
    (net (code "36") (name "LED8") (class "Default")
      (node (ref "LIGHT8") (pin "A") (pinfunction "A_A") (pintype "passive"))
      (node (ref "MC") (pin "27") (pinfunction "PB1_27") (pintype "bidirectional"))
    )
    (net (code "37") (name "Net-(120-1)") (class "Default")
      (node (ref "120") (pin "P$1") (pinfunction "1_P$1") (pintype "passive"))
      (node (ref "C5") (pin "1") (pinfunction "1_1") (pintype "passive"))
      (node (ref "U$6") (pin "P$6") (pinfunction "VOUT_P$6") (pintype "bidirectional"))
    )
    (net (code "38") (name "Net-(ARMED-PadA)") (class "Default")
      (node (ref "ARMED") (pin "A") (pinfunction "A_A") (pintype "passive"))
      (node (ref "R20") (pin "1") (pinfunction "1_1") (pintype "passive"))
    )
    (net (code "39") (name "Net-(CHARGING-PadC)") (class "Default")
      (node (ref "CHARGING") (pin "C") (pinfunction "C_C") (pintype "passive"))
      (node (ref "R14") (pin "2") (pinfunction "2_2") (pintype "passive"))
    )
    (net (code "40") (name "Net-(DISCHARGING-PadC)") (class "Default")
      (node (ref "DISCHARGING") (pin "C") (pinfunction "C_C") (pintype "passive"))
      (node (ref "R17") (pin "2") (pinfunction "2_2") (pintype "passive"))
    )
    (net (code "41") (name "Net-(LIGHT1-PadC)") (class "Default")
      (node (ref "LIGHT1") (pin "C") (pinfunction "C_C") (pintype "passive"))
      (node (ref "R18") (pin "2") (pinfunction "2_2") (pintype "passive"))
    )
    (net (code "42") (name "Net-(LIGHT2-PadC)") (class "Default")
      (node (ref "LIGHT2") (pin "C") (pinfunction "C_C") (pintype "passive"))
      (node (ref "R19") (pin "2") (pinfunction "2_2") (pintype "passive"))
    )
    (net (code "43") (name "Net-(LIGHT3-PadC)") (class "Default")
      (node (ref "LIGHT3") (pin "C") (pinfunction "C_C") (pintype "passive"))
      (node (ref "R22") (pin "2") (pinfunction "2_2") (pintype "passive"))
    )
    (net (code "44") (name "Net-(LIGHT4-PadC)") (class "Default")
      (node (ref "LIGHT4") (pin "C") (pinfunction "C_C") (pintype "passive"))
      (node (ref "R23") (pin "2") (pinfunction "2_2") (pintype "passive"))
    )
    (net (code "45") (name "Net-(LIGHT5-PadC)") (class "Default")
      (node (ref "LIGHT5") (pin "C") (pinfunction "C_C") (pintype "passive"))
      (node (ref "R24") (pin "2") (pinfunction "2_2") (pintype "passive"))
    )
    (net (code "46") (name "Net-(LIGHT6-PadC)") (class "Default")
      (node (ref "LIGHT6") (pin "C") (pinfunction "C_C") (pintype "passive"))
      (node (ref "R25") (pin "2") (pinfunction "2_2") (pintype "passive"))
    )
    (net (code "47") (name "Net-(LIGHT7-PadC)") (class "Default")
      (node (ref "LIGHT7") (pin "C") (pinfunction "C_C") (pintype "passive"))
      (node (ref "R26") (pin "2") (pinfunction "2_2") (pintype "passive"))
    )
    (net (code "48") (name "Net-(LIGHT8-PadC)") (class "Default")
      (node (ref "LIGHT8") (pin "C") (pinfunction "C_C") (pintype "passive"))
      (node (ref "R28") (pin "2") (pinfunction "2_2") (pintype "passive"))
    )
    (net (code "49") (name "Net-(MC-BOOT0)") (class "Default")
      (node (ref "MC") (pin "60") (pinfunction "BOOT0_60") (pintype "bidirectional"))
      (node (ref "R30") (pin "1") (pinfunction "1_1") (pintype "passive"))
    )
    (net (code "50") (name "Net-(MC-PC14{slash}OSC32_IN)") (class "Default")
      (node (ref "C9") (pin "1") (pinfunction "1_1") (pintype "passive"))
      (node (ref "MC") (pin "3") (pinfunction "PC14/OSC32_IN_3") (pintype "bidirectional"))
      (node (ref "Y3") (pin "P$1") (pinfunction "1_P$1") (pintype "passive"))
    )
    (net (code "51") (name "Net-(MC-PC15{slash}OSC32_OUT)") (class "Default")
      (node (ref "C13") (pin "1") (pinfunction "1_1") (pintype "passive"))
      (node (ref "MC") (pin "4") (pinfunction "PC15/OSC32_OUT_4") (pintype "bidirectional"))
      (node (ref "Y3") (pin "P$2") (pinfunction "2_P$2") (pintype "passive"))
    )
    (net (code "52") (name "Net-(MC-PH0{slash}OSC_IN)") (class "Default")
      (node (ref "C3") (pin "1") (pinfunction "1_1") (pintype "passive"))
      (node (ref "MC") (pin "5") (pinfunction "PH0/OSC_IN_5") (pintype "bidirectional"))
      (node (ref "Y1") (pin "2") (pinfunction "2_2") (pintype "passive"))
    )
    (net (code "53") (name "Net-(MC-PH1{slash}OSC_OUT)") (class "Default")
      (node (ref "C2") (pin "1") (pinfunction "1_1") (pintype "passive"))
      (node (ref "MC") (pin "6") (pinfunction "PH1/OSC_OUT_6") (pintype "bidirectional"))
      (node (ref "Y1") (pin "1") (pinfunction "1_1") (pintype "passive"))
    )
    (net (code "54") (name "Net-(MC-VCAP_1)") (class "Default")
      (node (ref "C7") (pin "2") (pinfunction "2_2") (pintype "passive"))
      (node (ref "MC") (pin "31") (pinfunction "VCAP_1_31") (pintype "power_in"))
    )
    (net (code "55") (name "Net-(MC-VCAP_2)") (class "Default")
      (node (ref "C8") (pin "2") (pinfunction "2_2") (pintype "passive"))
      (node (ref "MC") (pin "47") (pinfunction "VCAP_2_47") (pintype "power_in"))
    )
    (net (code "56") (name "Net-(Q2-D)") (class "Default")
      (node (ref "Q2") (pin "3") (pinfunction "D_3") (pintype "bidirectional"))
      (node (ref "R44") (pin "1") (pinfunction "1_1") (pintype "passive"))
    )
    (net (code "57") (name "Net-(Q3-D)") (class "Default")
      (node (ref "Q3") (pin "3") (pinfunction "D_3") (pintype "bidirectional"))
      (node (ref "R12") (pin "1") (pinfunction "1_1") (pintype "passive"))
    )
    (net (code "58") (name "Net-(Q6-G)") (class "Default")
      (node (ref "Q6") (pin "1") (pinfunction "G_1") (pintype "passive"))
      (node (ref "R12") (pin "2") (pinfunction "2_2") (pintype "passive"))
      (node (ref "R9") (pin "1") (pinfunction "1_1") (pintype "passive"))
    )
    (net (code "59") (name "Net-(Q18-G)") (class "Default")
      (node (ref "Q18") (pin "1") (pinfunction "G_1") (pintype "passive"))
      (node (ref "R43") (pin "1") (pinfunction "1_1") (pintype "passive"))
      (node (ref "R44") (pin "2") (pinfunction "2_2") (pintype "passive"))
    )
    (net (code "60") (name "Net-(R1-Pad1)") (class "Default")
      (node (ref "R1") (pin "1") (pinfunction "1_1") (pintype "passive"))
      (node (ref "USB_ID/USB_DP/USB_DN") (pin "D+") (pinfunction "D+_D+") (pintype "bidirectional"))
    )
    (net (code "61") (name "Net-(R11-Pad1)") (class "Default")
      (node (ref "R11") (pin "1") (pinfunction "1_1") (pintype "passive"))
      (node (ref "USB_ID/USB_DP/USB_DN") (pin "ID") (pinfunction "ID_ID") (pintype "bidirectional"))
    )
    (net (code "62") (name "Net-(R13-Pad1)") (class "Default")
      (node (ref "R13") (pin "1") (pinfunction "1_1") (pintype "passive"))
      (node (ref "USB_ID/USB_DP/USB_DN") (pin "D-") (pinfunction "D-_D-") (pintype "bidirectional"))
    )
    (net (code "63") (name "Net-(U1-CP1)") (class "Default")
      (node (ref "C18") (pin "2") (pinfunction "2_2") (pintype "passive"))
      (node (ref "U1") (pin "11") (pinfunction "CP1_11") (pintype "passive"))
    )
    (net (code "64") (name "Net-(U1-CP2)") (class "Default")
      (node (ref "C18") (pin "1") (pinfunction "1_1") (pintype "passive"))
      (node (ref "U1") (pin "12") (pinfunction "CP2_12") (pintype "passive"))
    )
    (net (code "65") (name "Net-(U1-SENSE)") (class "Default")
      (node (ref "R4") (pin "2") (pinfunction "2_2") (pintype "passive"))
      (node (ref "U1") (pin "8") (pinfunction "SENSE_8") (pintype "output"))
    )
    (net (code "66") (name "Net-(U1-VBB)") (class "Default")
      (node (ref "C16") (pin "1") (pinfunction "1_1") (pintype "passive"))
      (node (ref "C17") (pin "1") (pinfunction "1_1") (pintype "passive"))
      (node (ref "C19") (pin "1") (pinfunction "1_1") (pintype "passive"))
      (node (ref "U1") (pin "9") (pinfunction "VBB_9") (pintype "power_in"))
    )
    (net (code "67") (name "Net-(U1-VCP)") (class "Default")
      (node (ref "C17") (pin "2") (pinfunction "2_2") (pintype "passive"))
      (node (ref "U1") (pin "14") (pinfunction "VCP_14") (pintype "output"))
    )
    (net (code "68") (name "PWM_CLAW") (class "Default")
      (node (ref "CLAW_CONTROL") (pin "4") (pinfunction "4_4") (pintype "passive"))
      (node (ref "MC") (pin "14") (pinfunction "PA0/WKUP_14") (pintype "bidirectional"))
    )
    (net (code "69") (name "PWM_DRIVER1") (class "Default")
      (node (ref "MC") (pin "15") (pinfunction "PA1/USART2_RTS_15") (pintype "bidirectional"))
      (node (ref "U1") (pin "3") (pinfunction "IN1_3") (pintype "input"))
    )
    (net (code "70") (name "PWM_DRIVER2") (class "Default")
      (node (ref "MC") (pin "16") (pinfunction "PA2/USART2_TX_16") (pintype "bidirectional"))
      (node (ref "U1") (pin "16") (pinfunction "IN2_16") (pintype "input"))
    )
    (net (code "71") (name "PWM_OUT1") (class "Default")
      (node (ref "CLAW_CONTROL") (pin "5") (pinfunction "5_5") (pintype "passive"))
      (node (ref "U1") (pin "7") (pinfunction "OUT1_7") (pintype "output"))
    )
    (net (code "72") (name "PWM_OUT2") (class "Default")
      (node (ref "CLAW_CONTROL") (pin "6") (pinfunction "6_6") (pintype "passive"))
      (node (ref "U1") (pin "10") (pinfunction "OUT2_10") (pintype "output"))
    )
    (net (code "73") (name "RESET") (class "Default")
      (node (ref "JTAG_HEADER") (pin "15") (pinfunction "15_15") (pintype "passive"))
      (node (ref "MC") (pin "7") (pinfunction "NRST_7") (pintype "bidirectional"))
      (node (ref "R27") (pin "1") (pinfunction "1_1") (pintype "passive"))
      (node (ref "RESET_SWITCH") (pin "3") (pinfunction "2_3") (pintype "passive"))
    )
    (net (code "74") (name "SCL") (class "Default")
      (node (ref "MC") (pin "58") (pinfunction "PB6_58") (pintype "bidirectional"))
      (node (ref "U$1") (pin "31") (pinfunction "BOARD_SCL_31") (pintype "bidirectional"))
    )
    (net (code "75") (name "SDA") (class "Default")
      (node (ref "MC") (pin "59") (pinfunction "PB7_59") (pintype "bidirectional"))
      (node (ref "U$1") (pin "32") (pinfunction "BOARD_SDA_32") (pintype "bidirectional"))
    )
    (net (code "76") (name "SMBA") (class "Default")
      (node (ref "MC") (pin "57") (pinfunction "PB5_57") (pintype "bidirectional"))
    )
    (net (code "77") (name "SWD_CLK") (class "Default")
      (node (ref "JTAG_HEADER") (pin "9") (pinfunction "9_9") (pintype "passive"))
      (node (ref "MC") (pin "49") (pinfunction "PA14/JTCK-SWCLK_49") (pintype "bidirectional"))
    )
    (net (code "78") (name "SWD_IO") (class "Default")
      (node (ref "JTAG_HEADER") (pin "7") (pinfunction "7_7") (pintype "passive"))
      (node (ref "MC") (pin "46") (pinfunction "PA13/JMS-SWDIO_46") (pintype "bidirectional"))
    )
    (net (code "79") (name "TORPEDO1") (class "Default")
      (node (ref "Q18") (pin "3") (pinfunction "D_3") (pintype "passive"))
      (node (ref "TORPEDO_CONNECTOR") (pin "1") (pinfunction "1_1") (pintype "passive"))
    )
    (net (code "80") (name "TORPEDO1_GATE") (class "Default")
      (node (ref "MC") (pin "37") (pinfunction "PC6_37") (pintype "bidirectional"))
      (node (ref "Q2") (pin "1") (pinfunction "G_1") (pintype "bidirectional"))
    )
    (net (code "81") (name "TORPEDO2") (class "Default")
      (node (ref "Q6") (pin "3") (pinfunction "D_3") (pintype "passive"))
      (node (ref "TORPEDO_CONNECTOR") (pin "2") (pinfunction "2_2") (pintype "passive"))
    )
    (net (code "82") (name "TORPEDO2_GATE") (class "Default")
      (node (ref "MC") (pin "38") (pinfunction "PC7_38") (pintype "bidirectional"))
      (node (ref "Q3") (pin "1") (pinfunction "G_1") (pintype "bidirectional"))
    )
    (net (code "83") (name "USB_DN") (class "Default")
      (node (ref "MC") (pin "44") (pinfunction "PA11_44") (pintype "bidirectional"))
      (node (ref "R13") (pin "2") (pinfunction "2_2") (pintype "passive"))
    )
    (net (code "84") (name "USB_DP") (class "Default")
      (node (ref "MC") (pin "45") (pinfunction "PA12_45") (pintype "bidirectional"))
      (node (ref "R1") (pin "2") (pinfunction "2_2") (pintype "passive"))
    )
    (net (code "85") (name "USB_ID") (class "Default")
      (node (ref "R11") (pin "2") (pinfunction "2_2") (pintype "passive"))
      (node (ref "R2") (pin "1") (pinfunction "1_1") (pintype "passive"))
    )
    (net (code "86") (name "V+") (class "Default")
      (node (ref "POWER_INPUT") (pin "4") (pinfunction "4_4") (pintype "passive"))
      (node (ref "U$6") (pin "P$2") (pinfunction "VIN_P$2") (pintype "bidirectional"))
    )
    (net (code "87") (name "VBAT") (class "Default")
      (node (ref "MC") (pin "1") (pinfunction "VBAT_1") (pintype "power_in"))
    )
    (net (code "88") (name "VBUS") (class "Default")
      (node (ref "C14") (pin "1") (pinfunction "1_1") (pintype "passive"))
      (node (ref "USB_ID/USB_DP/USB_DN") (pin "VBUS") (pinfunction "VBUS_VBUS") (pintype "power_in"))
      (node (ref "VR1") (pin "3") (pinfunction "VIN_3") (pintype "input"))
    )
    (net (code "89") (name "unconnected-(JTAG_HEADER-Pad3)") (class "Default")
      (node (ref "JTAG_HEADER") (pin "3") (pinfunction "3_3") (pintype "passive"))
    )
    (net (code "90") (name "unconnected-(JTAG_HEADER-Pad5)") (class "Default")
      (node (ref "JTAG_HEADER") (pin "5") (pinfunction "5_5") (pintype "passive"))
    )
    (net (code "91") (name "unconnected-(JTAG_HEADER-Pad11)") (class "Default")
      (node (ref "JTAG_HEADER") (pin "11") (pinfunction "11_11") (pintype "passive"))
    )
    (net (code "92") (name "unconnected-(JTAG_HEADER-Pad13)") (class "Default")
      (node (ref "JTAG_HEADER") (pin "13") (pinfunction "13_13") (pintype "passive"))
    )
    (net (code "93") (name "unconnected-(JTAG_HEADER-Pad17)") (class "Default")
      (node (ref "JTAG_HEADER") (pin "17") (pinfunction "17_17") (pintype "passive"))
    )
    (net (code "94") (name "unconnected-(JTAG_HEADER-Pad19)") (class "Default")
      (node (ref "JTAG_HEADER") (pin "19") (pinfunction "19_19") (pintype "passive"))
    )
    (net (code "95") (name "unconnected-(MC-PA3{slash}USART2_RX-Pad17)") (class "Default")
      (node (ref "MC") (pin "17") (pinfunction "PA3/USART2_RX_17") (pintype "bidirectional"))
    )
    (net (code "96") (name "unconnected-(MC-PA8-Pad41)") (class "Default")
      (node (ref "MC") (pin "41") (pinfunction "PA8_41") (pintype "bidirectional"))
    )
    (net (code "97") (name "unconnected-(MC-PA9-Pad42)") (class "Default")
      (node (ref "MC") (pin "42") (pinfunction "PA9_42") (pintype "bidirectional"))
    )
    (net (code "98") (name "unconnected-(MC-PA10-Pad43)") (class "Default")
      (node (ref "MC") (pin "43") (pinfunction "PA10_43") (pintype "bidirectional"))
    )
    (net (code "99") (name "unconnected-(MC-PA15-Pad50)") (class "Default")
      (node (ref "MC") (pin "50") (pinfunction "PA15_50") (pintype "bidirectional"))
    )
    (net (code "100") (name "unconnected-(MC-PB2{slash}BOOT1-Pad28)") (class "Default")
      (node (ref "MC") (pin "28") (pinfunction "PB2/BOOT1_28") (pintype "bidirectional"))
    )
    (net (code "101") (name "unconnected-(MC-PC0-Pad8)") (class "Default")
      (node (ref "MC") (pin "8") (pinfunction "PC0_8") (pintype "bidirectional"))
    )
    (net (code "102") (name "unconnected-(MC-PC1-Pad9)") (class "Default")
      (node (ref "MC") (pin "9") (pinfunction "PC1_9") (pintype "bidirectional"))
    )
    (net (code "103") (name "unconnected-(MC-PC2{slash}SPI2_MISO-Pad10)") (class "Default")
      (node (ref "MC") (pin "10") (pinfunction "PC2/SPI2_MISO_10") (pintype "bidirectional"))
    )
    (net (code "104") (name "unconnected-(MC-PC3{slash}SPI2_MOSI-Pad11)") (class "Default")
      (node (ref "MC") (pin "11") (pinfunction "PC3/SPI2_MOSI_11") (pintype "bidirectional"))
    )
    (net (code "105") (name "unconnected-(MC-PC9-Pad40)") (class "Default")
      (node (ref "MC") (pin "40") (pinfunction "PC9_40") (pintype "bidirectional"))
    )
    (net (code "106") (name "unconnected-(MC-PC13{slash}RTC_OUT-Pad2)") (class "Default")
      (node (ref "MC") (pin "2") (pinfunction "PC13/RTC_OUT_2") (pintype "bidirectional"))
    )
    (net (code "107") (name "unconnected-(U$1-3.3V_ON{slash}OFF-Pad14)") (class "Default")
      (node (ref "U$1") (pin "14") (pinfunction "3.3V_ON/OFF_14") (pintype "bidirectional"))
    )
    (net (code "108") (name "unconnected-(U$1-5V_ON_OFF-Pad15)") (class "Default")
      (node (ref "U$1") (pin "15") (pinfunction "5V_ON_OFF_15") (pintype "bidirectional"))
    )
    (net (code "109") (name "unconnected-(U$1-12V_ON{slash}OFF-Pad16)") (class "Default")
      (node (ref "U$1") (pin "16") (pinfunction "12V_ON/OFF_16") (pintype "bidirectional"))
    )
    (net (code "110") (name "unconnected-(U$1-ACOUSTIC_ON{slash}OFF-Pad17)") (class "Default")
      (node (ref "U$1") (pin "17") (pinfunction "ACOUSTIC_ON/OFF_17") (pintype "bidirectional"))
    )
    (net (code "111") (name "unconnected-(U$1-JETSON_ON{slash}OFF-Pad18)") (class "Default")
      (node (ref "U$1") (pin "18") (pinfunction "JETSON_ON/OFF_18") (pintype "bidirectional"))
    )
    (net (code "112") (name "unconnected-(U$1-KILL_SWITCH-Pad37)") (class "Default")
      (node (ref "U$1") (pin "37") (pinfunction "KILL_SWITCH_37") (pintype "output"))
    )
    (net (code "113") (name "unconnected-(U$1-MOBO_ON{slash}OFF-Pad19)") (class "Default")
      (node (ref "U$1") (pin "19") (pinfunction "MOBO_ON/OFF_19") (pintype "bidirectional"))
    )
    (net (code "114") (name "unconnected-(U$1-PWM_1-Pad20)") (class "Default")
      (node (ref "U$1") (pin "20") (pinfunction "PWM_1_20") (pintype "bidirectional"))
    )
    (net (code "115") (name "unconnected-(U$1-PWM_2-Pad21)") (class "Default")
      (node (ref "U$1") (pin "21") (pinfunction "PWM_2_21") (pintype "bidirectional"))
    )
    (net (code "116") (name "unconnected-(U$1-PWM_3-Pad22)") (class "Default")
      (node (ref "U$1") (pin "22") (pinfunction "PWM_3_22") (pintype "bidirectional"))
    )
    (net (code "117") (name "unconnected-(U$1-PWM_4-Pad23)") (class "Default")
      (node (ref "U$1") (pin "23") (pinfunction "PWM_4_23") (pintype "bidirectional"))
    )
    (net (code "118") (name "unconnected-(U$1-PWM_5-Pad24)") (class "Default")
      (node (ref "U$1") (pin "24") (pinfunction "PWM_5_24") (pintype "bidirectional"))
    )
    (net (code "119") (name "unconnected-(U$1-PWM_6-Pad25)") (class "Default")
      (node (ref "U$1") (pin "25") (pinfunction "PWM_6_25") (pintype "bidirectional"))
    )
    (net (code "120") (name "unconnected-(U$1-PWM_7-Pad26)") (class "Default")
      (node (ref "U$1") (pin "26") (pinfunction "PWM_7_26") (pintype "bidirectional"))
    )
    (net (code "121") (name "unconnected-(U$1-PWM_8-Pad27)") (class "Default")
      (node (ref "U$1") (pin "27") (pinfunction "PWM_8_27") (pintype "bidirectional"))
    )
    (net (code "122") (name "unconnected-(U$1-SENSOR_SCL-Pad29)") (class "Default")
      (node (ref "U$1") (pin "29") (pinfunction "SENSOR_SCL_29") (pintype "bidirectional"))
    )
    (net (code "123") (name "unconnected-(U$1-SENSOR_SDA-Pad30)") (class "Default")
      (node (ref "U$1") (pin "30") (pinfunction "SENSOR_SDA_30") (pintype "bidirectional"))
    )
    (net (code "124") (name "unconnected-(U$1-SPARE1-Pad7)") (class "Default")
      (node (ref "U$1") (pin "7") (pinfunction "SPARE1_7") (pintype "bidirectional"))
    )
    (net (code "125") (name "unconnected-(U$1-SPARE3-Pad33)") (class "Default")
      (node (ref "U$1") (pin "33") (pinfunction "SPARE3_33") (pintype "bidirectional"))
    )
    (net (code "126") (name "unconnected-(U$1-SPARE4-Pad34)") (class "Default")
      (node (ref "U$1") (pin "34") (pinfunction "SPARE4_34") (pintype "bidirectional"))
    )
    (net (code "127") (name "unconnected-(U$1-SPARE8-Pad50)") (class "Default")
      (node (ref "U$1") (pin "50") (pinfunction "SPARE8_50") (pintype "bidirectional"))
    )
    (net (code "128") (name "unconnected-(U$1-SWITCH_1-Pad38)") (class "Default")
      (node (ref "U$1") (pin "38") (pinfunction "SWITCH_1_38") (pintype "output"))
    )
    (net (code "129") (name "unconnected-(U$1-SWITCH_2-Pad39)") (class "Default")
      (node (ref "U$1") (pin "39") (pinfunction "SWITCH_2_39") (pintype "output"))
    )
    (net (code "130") (name "unconnected-(U$1-SWITCH_3-Pad40)") (class "Default")
      (node (ref "U$1") (pin "40") (pinfunction "SWITCH_3_40") (pintype "output"))
    )
    (net (code "131") (name "unconnected-(U$1-SWITCH_4-Pad41)") (class "Default")
      (node (ref "U$1") (pin "41") (pinfunction "SWITCH_4_41") (pintype "output"))
    )
    (net (code "132") (name "unconnected-(U$1-SWITCH_5-Pad42)") (class "Default")
      (node (ref "U$1") (pin "42") (pinfunction "SWITCH_5_42") (pintype "output"))
    )
    (net (code "133") (name "unconnected-(U1-NFAULT-Pad1)") (class "Default")
      (node (ref "U1") (pin "1") (pinfunction "NFAULT_1") (pintype "output"))
    )
    (net (code "134") (name "unconnected-(U1-VPROPI-Pad15)") (class "Default")
      (node (ref "U1") (pin "15") (pinfunction "VPROPI_15") (pintype "output"))
    )
    (net (code "135") (name "unconnected-(VR1-VOUT_4-Pad4)") (class "Default")
      (node (ref "VR1") (pin "4") (pinfunction "VOUT_4_4") (pintype "output"))
    )
  )
)
